# DDR.net
KiCad netlist of a schematic drawn in Altium Designer
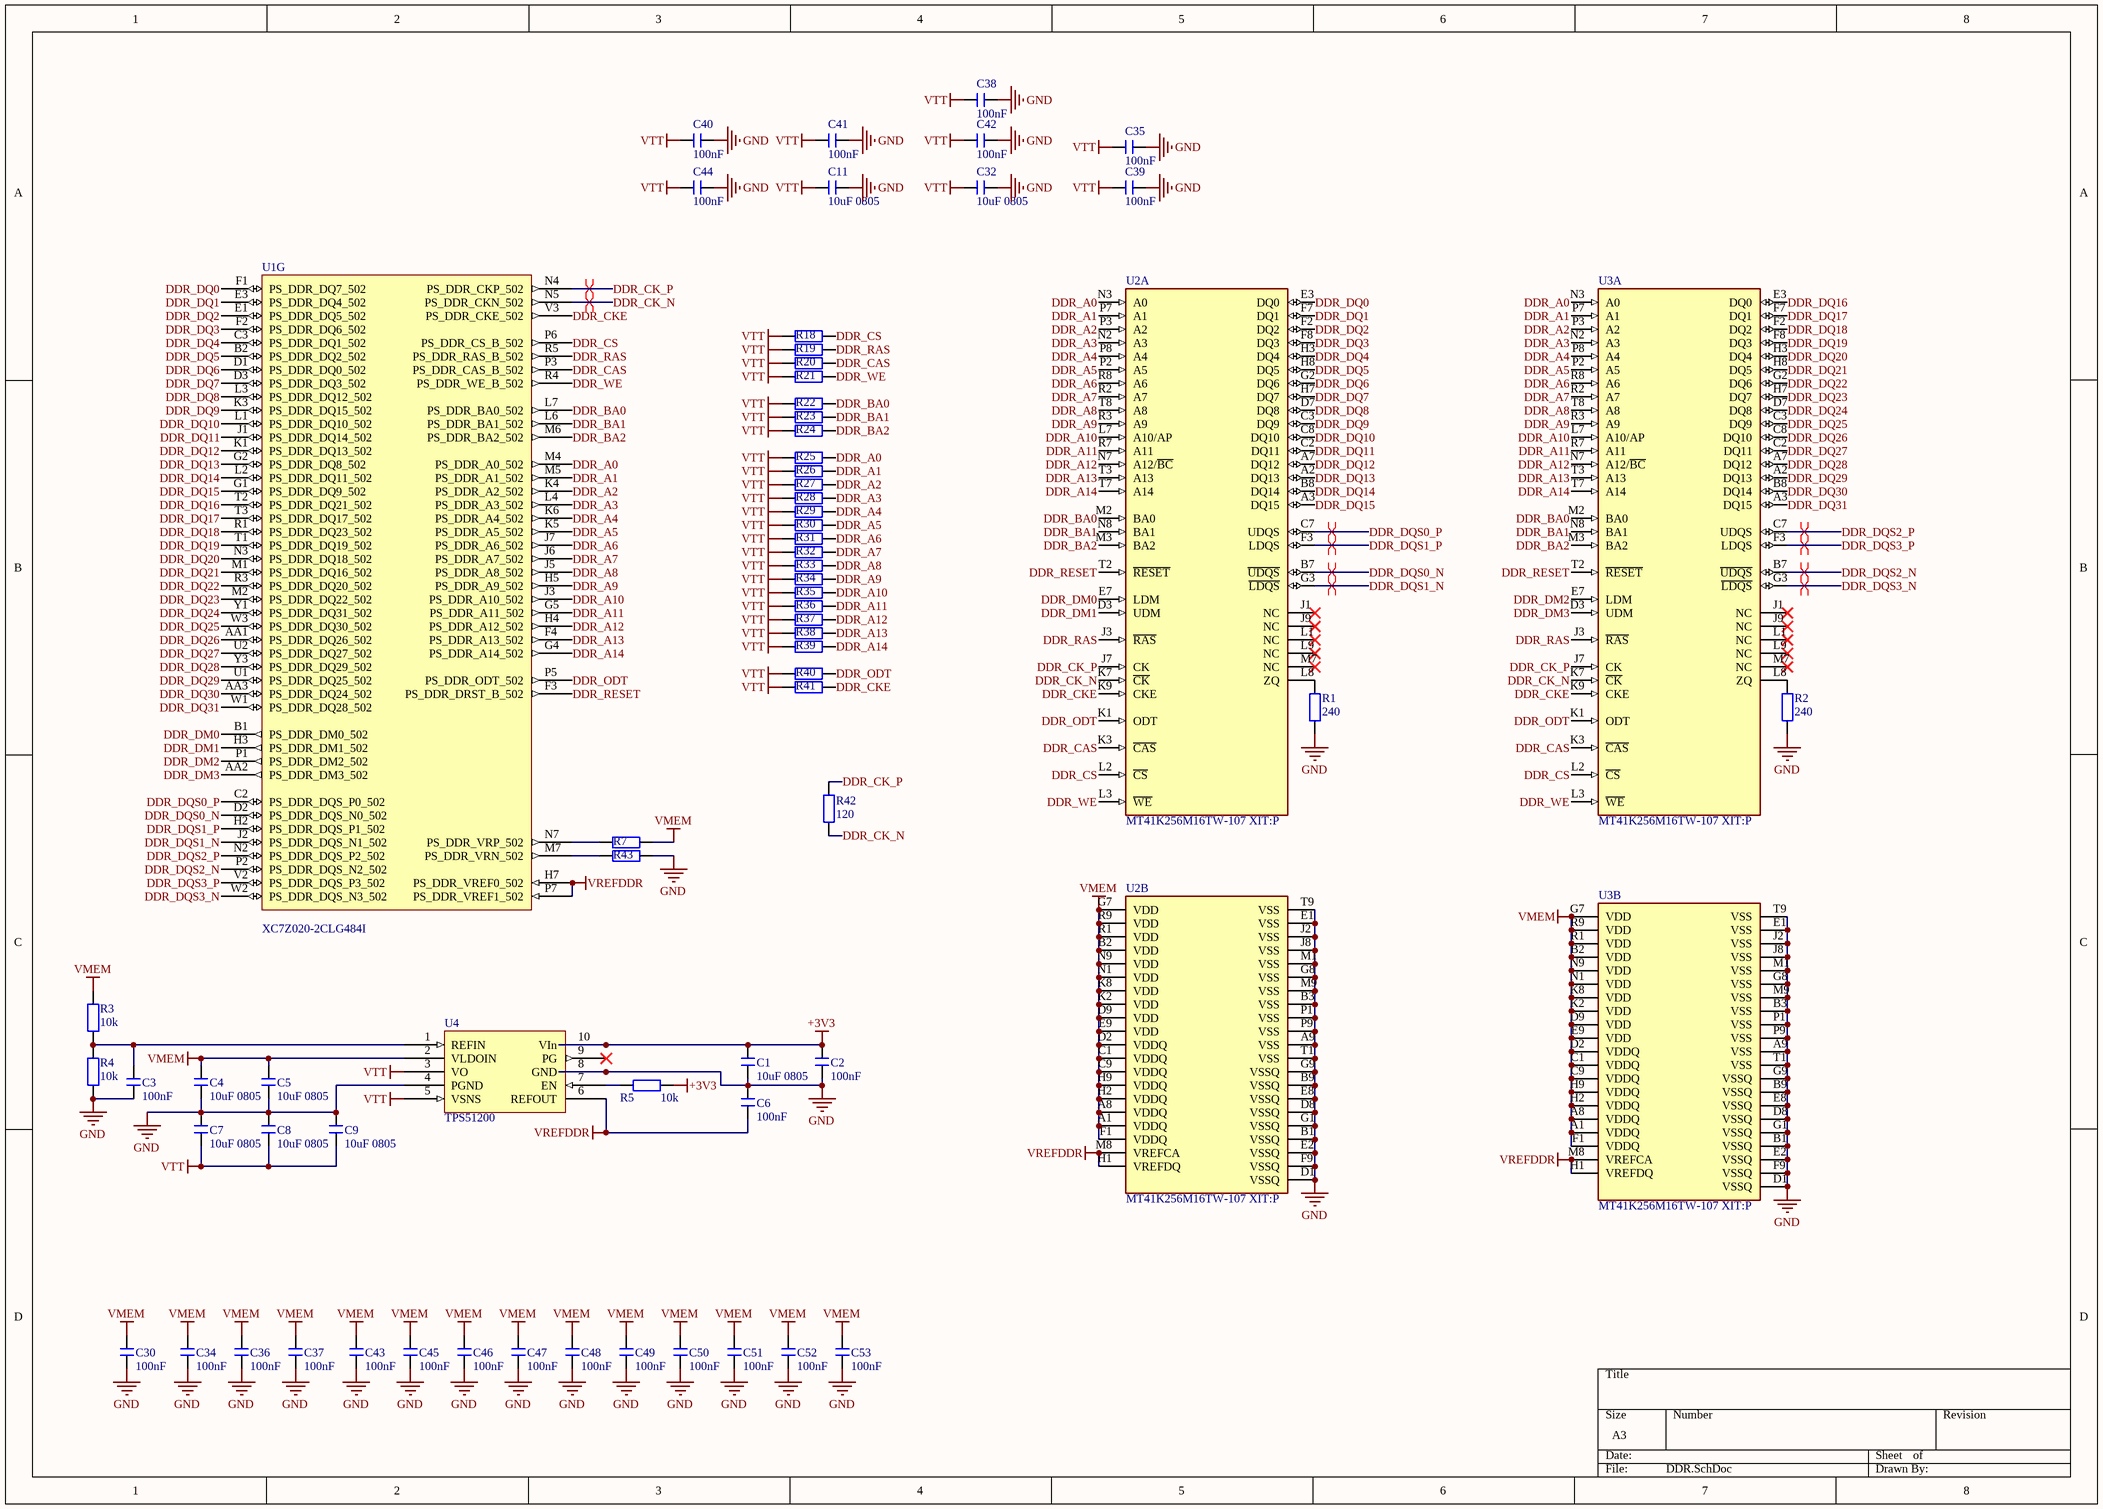
[diagram p0: DDR.SchDoc]

(export (version "E")
  (design (tool "Eeschema 10.0.6"))
  (components
    (comp (ref "C1") (value "10uF 0805") (footprint "C0603") (libsource (lib "Passive") (part "C")))
    (comp (ref "C2") (value "100nF") (footprint "C0402") (libsource (lib "Passive") (part "C")))
    (comp (ref "C3") (value "100nF") (footprint "C0402") (libsource (lib "Passive") (part "C")))
    (comp (ref "C4") (value "10uF 0805") (footprint "C0603") (libsource (lib "Passive") (part "C")))
    (comp (ref "C5") (value "10uF 0805") (footprint "C0603") (libsource (lib "Passive") (part "C")))
    (comp (ref "C6") (value "100nF") (footprint "C0402") (libsource (lib "Passive") (part "C")))
    (comp (ref "C7") (value "10uF 0805") (footprint "C0603") (libsource (lib "Passive") (part "C")))
    (comp (ref "C8") (value "10uF 0805") (footprint "C0603") (libsource (lib "Passive") (part "C")))
    (comp (ref "C9") (value "10uF 0805") (footprint "C0603") (libsource (lib "Passive") (part "C")))
    (comp (ref "C11") (value "10uF 0805") (footprint "C0603") (libsource (lib "Passive") (part "C")))
    (comp (ref "C30") (value "100nF") (footprint "C0402") (libsource (lib "Passive") (part "C")))
    (comp (ref "C32") (value "10uF 0805") (footprint "C0603") (libsource (lib "Passive") (part "C")))
    (comp (ref "C34") (value "100nF") (footprint "C0402") (libsource (lib "Passive") (part "C")))
    (comp (ref "C35") (value "100nF") (footprint "C0402") (libsource (lib "Passive") (part "C")))
    (comp (ref "C36") (value "100nF") (footprint "C0402") (libsource (lib "Passive") (part "C")))
    (comp (ref "C37") (value "100nF") (footprint "C0402") (libsource (lib "Passive") (part "C")))
    (comp (ref "C38") (value "100nF") (footprint "C0402") (libsource (lib "Passive") (part "C")))
    (comp (ref "C39") (value "100nF") (footprint "C0402") (libsource (lib "Passive") (part "C")))
    (comp (ref "C40") (value "100nF") (footprint "C0402") (libsource (lib "Passive") (part "C")))
    (comp (ref "C41") (value "100nF") (footprint "C0402") (libsource (lib "Passive") (part "C")))
    (comp (ref "C42") (value "100nF") (footprint "C0402") (libsource (lib "Passive") (part "C")))
    (comp (ref "C43") (value "100nF") (footprint "C0402") (libsource (lib "Passive") (part "C")))
    (comp (ref "C44") (value "100nF") (footprint "C0402") (libsource (lib "Passive") (part "C")))
    (comp (ref "C45") (value "100nF") (footprint "C0402") (libsource (lib "Passive") (part "C")))
    (comp (ref "C46") (value "100nF") (footprint "C0402") (libsource (lib "Passive") (part "C")))
    (comp (ref "C47") (value "100nF") (footprint "C0402") (libsource (lib "Passive") (part "C")))
    (comp (ref "C48") (value "100nF") (footprint "C0402") (libsource (lib "Passive") (part "C")))
    (comp (ref "C49") (value "100nF") (footprint "C0402") (libsource (lib "Passive") (part "C")))
    (comp (ref "C50") (value "100nF") (footprint "C0402") (libsource (lib "Passive") (part "C")))
    (comp (ref "C51") (value "100nF") (footprint "C0402") (libsource (lib "Passive") (part "C")))
    (comp (ref "C52") (value "100nF") (footprint "C0402") (libsource (lib "Passive") (part "C")))
    (comp (ref "C53") (value "100nF") (footprint "C0402") (libsource (lib "Passive") (part "C")))
    (comp (ref "R1") (value "240") (footprint "R0402") (libsource (lib "Passive") (part "R")))
    (comp (ref "R2") (value "240") (footprint "R0402") (libsource (lib "Passive") (part "R")))
    (comp (ref "R3") (value "10k") (footprint "R0402") (libsource (lib "Passive") (part "R")))
    (comp (ref "R4") (value "10k") (footprint "R0402") (libsource (lib "Passive") (part "R")))
    (comp (ref "R5") (value "10k") (footprint "R0402") (libsource (lib "Passive") (part "R")))
    (comp (ref "R7") (value "49.9") (footprint "R0402") (libsource (lib "Passive") (part "R")))
    (comp (ref "R18") (value "49.9") (footprint "R0402") (libsource (lib "Passive") (part "R")))
    (comp (ref "R19") (value "49.9") (footprint "R0402") (libsource (lib "Passive") (part "R")))
    (comp (ref "R20") (value "49.9") (footprint "R0402") (libsource (lib "Passive") (part "R")))
    (comp (ref "R21") (value "49.9") (footprint "R0402") (libsource (lib "Passive") (part "R")))
    (comp (ref "R22") (value "49.9") (footprint "R0402") (libsource (lib "Passive") (part "R")))
    (comp (ref "R23") (value "49.9") (footprint "R0402") (libsource (lib "Passive") (part "R")))
    (comp (ref "R24") (value "49.9") (footprint "R0402") (libsource (lib "Passive") (part "R")))
    (comp (ref "R25") (value "49.9") (footprint "R0402") (libsource (lib "Passive") (part "R")))
    (comp (ref "R26") (value "49.9") (footprint "R0402") (libsource (lib "Passive") (part "R")))
    (comp (ref "R27") (value "49.9") (footprint "R0402") (libsource (lib "Passive") (part "R")))
    (comp (ref "R28") (value "49.9") (footprint "R0402") (libsource (lib "Passive") (part "R")))
    (comp (ref "R29") (value "49.9") (footprint "R0402") (libsource (lib "Passive") (part "R")))
    (comp (ref "R30") (value "49.9") (footprint "R0402") (libsource (lib "Passive") (part "R")))
    (comp (ref "R31") (value "49.9") (footprint "R0402") (libsource (lib "Passive") (part "R")))
    (comp (ref "R32") (value "49.9") (footprint "R0402") (libsource (lib "Passive") (part "R")))
    (comp (ref "R33") (value "49.9") (footprint "R0402") (libsource (lib "Passive") (part "R")))
    (comp (ref "R34") (value "49.9") (footprint "R0402") (libsource (lib "Passive") (part "R")))
    (comp (ref "R35") (value "49.9") (footprint "R0402") (libsource (lib "Passive") (part "R")))
    (comp (ref "R36") (value "49.9") (footprint "R0402") (libsource (lib "Passive") (part "R")))
    (comp (ref "R37") (value "49.9") (footprint "R0402") (libsource (lib "Passive") (part "R")))
    (comp (ref "R38") (value "49.9") (footprint "R0402") (libsource (lib "Passive") (part "R")))
    (comp (ref "R39") (value "49.9") (footprint "R0402") (libsource (lib "Passive") (part "R")))
    (comp (ref "R40") (value "49.9") (footprint "R0402") (libsource (lib "Passive") (part "R")))
    (comp (ref "R41") (value "49.9") (footprint "R0402") (libsource (lib "Passive") (part "R")))
    (comp (ref "R42") (value "120") (footprint "R0402") (libsource (lib "Passive") (part "R")))
    (comp (ref "R43") (value "49.9") (footprint "R0402") (libsource (lib "Passive") (part "R")))
    (comp (ref "U1")
      (value "XC7Z020-2CLG484I")
      (footprint "CLG484")
      (fields (field (name "GENERIC PART NUMBER") "XC7Z020"))
      (libsource (lib "Altium Content Vault") (part "XNLX-XC7Z020-CLG484"))
    )
    (comp (ref "U2")
      (value "MT41K256M16TW-107 XIT:P")
      (footprint "FP-TW-MFG")
      (description "IC DRAM 4GBIT PARALLEL 96FBGA")
      (libsource (lib "Altium Content Vault") (part "c1579f81ec1b908b919197b6bca2eab"))
    )
    (comp (ref "U3")
      (value "MT41K256M16TW-107 XIT:P")
      (footprint "FP-TW-MFG")
      (description "IC DRAM 4GBIT PARALLEL 96FBGA")
      (libsource (lib "Altium Content Vault") (part "c1579f81ec1b908b919197b6bca2eab"))
    )
    (comp (ref "U4")
      (value "TPS51200")
      (footprint "SON50P300X100_HS-11N")
      (description "Sink and Source DDR Termination Regulator")
      (libsource (lib "TI") (part "TPS51200"))
    )
  )
  (nets
    (net (code "1") (name "+3V3") (class "Default")
      (node (ref "C1") (pin "2") (pinfunction "2_2") (pintype "passive"))
      (node (ref "C2") (pin "2") (pinfunction "2_2") (pintype "passive"))
      (node (ref "R5") (pin "2") (pinfunction "2_2") (pintype "passive"))
      (node (ref "U4") (pin "10") (pinfunction "VIn_10") (pintype "power_in"))
    )
    (net (code "2") (name "/DDR_A0") (class "Default")
      (node (ref "R25") (pin "2") (pinfunction "2_2") (pintype "passive"))
      (node (ref "U1") (pin "M4") (pinfunction "PS_DDR_A0_502_M4") (pintype "output"))
      (node (ref "U2") (pin "N3") (pinfunction "A0_N3") (pintype "input"))
      (node (ref "U3") (pin "N3") (pinfunction "A0_N3") (pintype "input"))
    )
    (net (code "3") (name "/DDR_A1") (class "Default")
      (node (ref "R26") (pin "2") (pinfunction "2_2") (pintype "passive"))
      (node (ref "U1") (pin "M5") (pinfunction "PS_DDR_A1_502_M5") (pintype "output"))
      (node (ref "U2") (pin "P7") (pinfunction "A1_P7") (pintype "input"))
      (node (ref "U3") (pin "P7") (pinfunction "A1_P7") (pintype "input"))
    )
    (net (code "4") (name "/DDR_A2") (class "Default")
      (node (ref "R27") (pin "2") (pinfunction "2_2") (pintype "passive"))
      (node (ref "U1") (pin "K4") (pinfunction "PS_DDR_A2_502_K4") (pintype "output"))
      (node (ref "U2") (pin "P3") (pinfunction "A2_P3") (pintype "input"))
      (node (ref "U3") (pin "P3") (pinfunction "A2_P3") (pintype "input"))
    )
    (net (code "5") (name "/DDR_A3") (class "Default")
      (node (ref "R28") (pin "2") (pinfunction "2_2") (pintype "passive"))
      (node (ref "U1") (pin "L4") (pinfunction "PS_DDR_A3_502_L4") (pintype "output"))
      (node (ref "U2") (pin "N2") (pinfunction "A3_N2") (pintype "input"))
      (node (ref "U3") (pin "N2") (pinfunction "A3_N2") (pintype "input"))
    )
    (net (code "6") (name "/DDR_A4") (class "Default")
      (node (ref "R29") (pin "2") (pinfunction "2_2") (pintype "passive"))
      (node (ref "U1") (pin "K6") (pinfunction "PS_DDR_A4_502_K6") (pintype "output"))
      (node (ref "U2") (pin "P8") (pinfunction "A4_P8") (pintype "input"))
      (node (ref "U3") (pin "P8") (pinfunction "A4_P8") (pintype "input"))
    )
    (net (code "7") (name "/DDR_A5") (class "Default")
      (node (ref "R30") (pin "2") (pinfunction "2_2") (pintype "passive"))
      (node (ref "U1") (pin "K5") (pinfunction "PS_DDR_A5_502_K5") (pintype "output"))
      (node (ref "U2") (pin "P2") (pinfunction "A5_P2") (pintype "input"))
      (node (ref "U3") (pin "P2") (pinfunction "A5_P2") (pintype "input"))
    )
    (net (code "8") (name "/DDR_A6") (class "Default")
      (node (ref "R31") (pin "2") (pinfunction "2_2") (pintype "passive"))
      (node (ref "U1") (pin "J7") (pinfunction "PS_DDR_A6_502_J7") (pintype "output"))
      (node (ref "U2") (pin "R8") (pinfunction "A6_R8") (pintype "input"))
      (node (ref "U3") (pin "R8") (pinfunction "A6_R8") (pintype "input"))
    )
    (net (code "9") (name "/DDR_A7") (class "Default")
      (node (ref "R32") (pin "2") (pinfunction "2_2") (pintype "passive"))
      (node (ref "U1") (pin "J6") (pinfunction "PS_DDR_A7_502_J6") (pintype "output"))
      (node (ref "U2") (pin "R2") (pinfunction "A7_R2") (pintype "input"))
      (node (ref "U3") (pin "R2") (pinfunction "A7_R2") (pintype "input"))
    )
    (net (code "10") (name "/DDR_A8") (class "Default")
      (node (ref "R33") (pin "2") (pinfunction "2_2") (pintype "passive"))
      (node (ref "U1") (pin "J5") (pinfunction "PS_DDR_A8_502_J5") (pintype "output"))
      (node (ref "U2") (pin "T8") (pinfunction "A8_T8") (pintype "input"))
      (node (ref "U3") (pin "T8") (pinfunction "A8_T8") (pintype "input"))
    )
    (net (code "11") (name "/DDR_A9") (class "Default")
      (node (ref "R34") (pin "2") (pinfunction "2_2") (pintype "passive"))
      (node (ref "U1") (pin "H5") (pinfunction "PS_DDR_A9_502_H5") (pintype "output"))
      (node (ref "U2") (pin "R3") (pinfunction "A9_R3") (pintype "input"))
      (node (ref "U3") (pin "R3") (pinfunction "A9_R3") (pintype "input"))
    )
    (net (code "12") (name "/DDR_A10") (class "Default")
      (node (ref "R35") (pin "2") (pinfunction "2_2") (pintype "passive"))
      (node (ref "U1") (pin "J3") (pinfunction "PS_DDR_A10_502_J3") (pintype "output"))
      (node (ref "U2") (pin "L7") (pinfunction "A10/AP_L7") (pintype "input"))
      (node (ref "U3") (pin "L7") (pinfunction "A10/AP_L7") (pintype "input"))
    )
    (net (code "13") (name "/DDR_A11") (class "Default")
      (node (ref "R36") (pin "2") (pinfunction "2_2") (pintype "passive"))
      (node (ref "U1") (pin "G5") (pinfunction "PS_DDR_A11_502_G5") (pintype "output"))
      (node (ref "U2") (pin "R7") (pinfunction "A11_R7") (pintype "input"))
      (node (ref "U3") (pin "R7") (pinfunction "A11_R7") (pintype "input"))
    )
    (net (code "14") (name "/DDR_A12") (class "Default")
      (node (ref "R37") (pin "2") (pinfunction "2_2") (pintype "passive"))
      (node (ref "U1") (pin "H4") (pinfunction "PS_DDR_A12_502_H4") (pintype "output"))
      (node (ref "U2") (pin "N7") (pinfunction "A12/~{BC}_N7") (pintype "input"))
      (node (ref "U3") (pin "N7") (pinfunction "A12/~{BC}_N7") (pintype "input"))
    )
    (net (code "15") (name "/DDR_A13") (class "Default")
      (node (ref "R38") (pin "2") (pinfunction "2_2") (pintype "passive"))
      (node (ref "U1") (pin "F4") (pinfunction "PS_DDR_A13_502_F4") (pintype "output"))
      (node (ref "U2") (pin "T3") (pinfunction "A13_T3") (pintype "input"))
      (node (ref "U3") (pin "T3") (pinfunction "A13_T3") (pintype "input"))
    )
    (net (code "16") (name "/DDR_A14") (class "Default")
      (node (ref "R39") (pin "2") (pinfunction "2_2") (pintype "passive"))
      (node (ref "U1") (pin "G4") (pinfunction "PS_DDR_A14_502_G4") (pintype "output"))
      (node (ref "U2") (pin "T7") (pinfunction "A14_T7") (pintype "input"))
      (node (ref "U3") (pin "T7") (pinfunction "A14_T7") (pintype "input"))
    )
    (net (code "17") (name "/DDR_BA0") (class "Default")
      (node (ref "R22") (pin "2") (pinfunction "2_2") (pintype "passive"))
      (node (ref "U1") (pin "L7") (pinfunction "PS_DDR_BA0_502_L7") (pintype "output"))
      (node (ref "U2") (pin "M2") (pinfunction "BA0_M2") (pintype "input"))
      (node (ref "U3") (pin "M2") (pinfunction "BA0_M2") (pintype "input"))
    )
    (net (code "18") (name "/DDR_BA1") (class "Default")
      (node (ref "R23") (pin "2") (pinfunction "2_2") (pintype "passive"))
      (node (ref "U1") (pin "L6") (pinfunction "PS_DDR_BA1_502_L6") (pintype "output"))
      (node (ref "U2") (pin "N8") (pinfunction "BA1_N8") (pintype "input"))
      (node (ref "U3") (pin "N8") (pinfunction "BA1_N8") (pintype "input"))
    )
    (net (code "19") (name "/DDR_BA2") (class "Default")
      (node (ref "R24") (pin "2") (pinfunction "2_2") (pintype "passive"))
      (node (ref "U1") (pin "M6") (pinfunction "PS_DDR_BA2_502_M6") (pintype "output"))
      (node (ref "U2") (pin "M3") (pinfunction "BA2_M3") (pintype "input"))
      (node (ref "U3") (pin "M3") (pinfunction "BA2_M3") (pintype "input"))
    )
    (net (code "20") (name "/DDR_CAS") (class "Default")
      (node (ref "R20") (pin "2") (pinfunction "2_2") (pintype "passive"))
      (node (ref "U1") (pin "P3") (pinfunction "PS_DDR_CAS_B_502_P3") (pintype "output"))
      (node (ref "U2") (pin "K3") (pinfunction "~{CAS}_K3") (pintype "input"))
      (node (ref "U3") (pin "K3") (pinfunction "~{CAS}_K3") (pintype "input"))
    )
    (net (code "21") (name "/DDR_CKE") (class "Default")
      (node (ref "R41") (pin "2") (pinfunction "2_2") (pintype "passive"))
      (node (ref "U1") (pin "V3") (pinfunction "PS_DDR_CKE_502_V3") (pintype "output"))
      (node (ref "U2") (pin "K9") (pinfunction "CKE_K9") (pintype "input"))
      (node (ref "U3") (pin "K9") (pinfunction "CKE_K9") (pintype "input"))
    )
    (net (code "22") (name "/DDR_CK_N") (class "Default")
      (node (ref "R42") (pin "1") (pinfunction "1_1") (pintype "passive"))
      (node (ref "U1") (pin "N5") (pinfunction "PS_DDR_CKN_502_N5") (pintype "output"))
      (node (ref "U2") (pin "K7") (pinfunction "~{CK}_K7") (pintype "input"))
      (node (ref "U3") (pin "K7") (pinfunction "~{CK}_K7") (pintype "input"))
    )
    (net (code "23") (name "/DDR_CK_P") (class "Default")
      (node (ref "R42") (pin "2") (pinfunction "2_2") (pintype "passive"))
      (node (ref "U1") (pin "N4") (pinfunction "PS_DDR_CKP_502_N4") (pintype "output"))
      (node (ref "U2") (pin "J7") (pinfunction "CK_J7") (pintype "input"))
      (node (ref "U3") (pin "J7") (pinfunction "CK_J7") (pintype "input"))
    )
    (net (code "24") (name "/DDR_CS") (class "Default")
      (node (ref "R18") (pin "2") (pinfunction "2_2") (pintype "passive"))
      (node (ref "U1") (pin "P6") (pinfunction "PS_DDR_CS_B_502_P6") (pintype "output"))
      (node (ref "U2") (pin "L2") (pinfunction "~{CS}_L2") (pintype "input"))
      (node (ref "U3") (pin "L2") (pinfunction "~{CS}_L2") (pintype "input"))
    )
    (net (code "25") (name "/DDR_DM0") (class "Default")
      (node (ref "U1") (pin "B1") (pinfunction "PS_DDR_DM0_502_B1") (pintype "output"))
      (node (ref "U2") (pin "E7") (pinfunction "LDM_E7") (pintype "input"))
    )
    (net (code "26") (name "/DDR_DM1") (class "Default")
      (node (ref "U1") (pin "H3") (pinfunction "PS_DDR_DM1_502_H3") (pintype "output"))
      (node (ref "U2") (pin "D3") (pinfunction "UDM_D3") (pintype "input"))
    )
    (net (code "27") (name "/DDR_DM2") (class "Default")
      (node (ref "U1") (pin "P1") (pinfunction "PS_DDR_DM2_502_P1") (pintype "output"))
      (node (ref "U3") (pin "E7") (pinfunction "LDM_E7") (pintype "input"))
    )
    (net (code "28") (name "/DDR_DM3") (class "Default")
      (node (ref "U1") (pin "AA2") (pinfunction "PS_DDR_DM3_502_AA2") (pintype "output"))
      (node (ref "U3") (pin "D3") (pinfunction "UDM_D3") (pintype "input"))
    )
    (net (code "29") (name "/DDR_DQ0") (class "Default")
      (node (ref "U1") (pin "F1") (pinfunction "PS_DDR_DQ7_502_F1") (pintype "bidirectional"))
      (node (ref "U2") (pin "E3") (pinfunction "DQ0_E3") (pintype "bidirectional"))
    )
    (net (code "30") (name "/DDR_DQ1") (class "Default")
      (node (ref "U1") (pin "E3") (pinfunction "PS_DDR_DQ4_502_E3") (pintype "bidirectional"))
      (node (ref "U2") (pin "F7") (pinfunction "DQ1_F7") (pintype "bidirectional"))
    )
    (net (code "31") (name "/DDR_DQ2") (class "Default")
      (node (ref "U1") (pin "E1") (pinfunction "PS_DDR_DQ5_502_E1") (pintype "bidirectional"))
      (node (ref "U2") (pin "F2") (pinfunction "DQ2_F2") (pintype "bidirectional"))
    )
    (net (code "32") (name "/DDR_DQ3") (class "Default")
      (node (ref "U1") (pin "F2") (pinfunction "PS_DDR_DQ6_502_F2") (pintype "bidirectional"))
      (node (ref "U2") (pin "F8") (pinfunction "DQ3_F8") (pintype "bidirectional"))
    )
    (net (code "33") (name "/DDR_DQ4") (class "Default")
      (node (ref "U1") (pin "C3") (pinfunction "PS_DDR_DQ1_502_C3") (pintype "bidirectional"))
      (node (ref "U2") (pin "H3") (pinfunction "DQ4_H3") (pintype "bidirectional"))
    )
    (net (code "34") (name "/DDR_DQ5") (class "Default")
      (node (ref "U1") (pin "B2") (pinfunction "PS_DDR_DQ2_502_B2") (pintype "bidirectional"))
      (node (ref "U2") (pin "H8") (pinfunction "DQ5_H8") (pintype "bidirectional"))
    )
    (net (code "35") (name "/DDR_DQ6") (class "Default")
      (node (ref "U1") (pin "D1") (pinfunction "PS_DDR_DQ0_502_D1") (pintype "bidirectional"))
      (node (ref "U2") (pin "G2") (pinfunction "DQ6_G2") (pintype "bidirectional"))
    )
    (net (code "36") (name "/DDR_DQ7") (class "Default")
      (node (ref "U1") (pin "D3") (pinfunction "PS_DDR_DQ3_502_D3") (pintype "bidirectional"))
      (node (ref "U2") (pin "H7") (pinfunction "DQ7_H7") (pintype "bidirectional"))
    )
    (net (code "37") (name "/DDR_DQ8") (class "Default")
      (node (ref "U1") (pin "L3") (pinfunction "PS_DDR_DQ12_502_L3") (pintype "bidirectional"))
      (node (ref "U2") (pin "D7") (pinfunction "DQ8_D7") (pintype "bidirectional"))
    )
    (net (code "38") (name "/DDR_DQ9") (class "Default")
      (node (ref "U1") (pin "K3") (pinfunction "PS_DDR_DQ15_502_K3") (pintype "bidirectional"))
      (node (ref "U2") (pin "C3") (pinfunction "DQ9_C3") (pintype "bidirectional"))
    )
    (net (code "39") (name "/DDR_DQ10") (class "Default")
      (node (ref "U1") (pin "L1") (pinfunction "PS_DDR_DQ10_502_L1") (pintype "bidirectional"))
      (node (ref "U2") (pin "C8") (pinfunction "DQ10_C8") (pintype "bidirectional"))
    )
    (net (code "40") (name "/DDR_DQ11") (class "Default")
      (node (ref "U1") (pin "J1") (pinfunction "PS_DDR_DQ14_502_J1") (pintype "bidirectional"))
      (node (ref "U2") (pin "C2") (pinfunction "DQ11_C2") (pintype "bidirectional"))
    )
    (net (code "41") (name "/DDR_DQ12") (class "Default")
      (node (ref "U1") (pin "K1") (pinfunction "PS_DDR_DQ13_502_K1") (pintype "bidirectional"))
      (node (ref "U2") (pin "A7") (pinfunction "DQ12_A7") (pintype "bidirectional"))
    )
    (net (code "42") (name "/DDR_DQ13") (class "Default")
      (node (ref "U1") (pin "G2") (pinfunction "PS_DDR_DQ8_502_G2") (pintype "bidirectional"))
      (node (ref "U2") (pin "A2") (pinfunction "DQ13_A2") (pintype "bidirectional"))
    )
    (net (code "43") (name "/DDR_DQ14") (class "Default")
      (node (ref "U1") (pin "L2") (pinfunction "PS_DDR_DQ11_502_L2") (pintype "bidirectional"))
      (node (ref "U2") (pin "B8") (pinfunction "DQ14_B8") (pintype "bidirectional"))
    )
    (net (code "44") (name "/DDR_DQ15") (class "Default")
      (node (ref "U1") (pin "G1") (pinfunction "PS_DDR_DQ9_502_G1") (pintype "bidirectional"))
      (node (ref "U2") (pin "A3") (pinfunction "DQ15_A3") (pintype "bidirectional"))
    )
    (net (code "45") (name "/DDR_DQ16") (class "Default")
      (node (ref "U1") (pin "T2") (pinfunction "PS_DDR_DQ21_502_T2") (pintype "bidirectional"))
      (node (ref "U3") (pin "E3") (pinfunction "DQ0_E3") (pintype "bidirectional"))
    )
    (net (code "46") (name "/DDR_DQ17") (class "Default")
      (node (ref "U1") (pin "T3") (pinfunction "PS_DDR_DQ17_502_T3") (pintype "bidirectional"))
      (node (ref "U3") (pin "F7") (pinfunction "DQ1_F7") (pintype "bidirectional"))
    )
    (net (code "47") (name "/DDR_DQ18") (class "Default")
      (node (ref "U1") (pin "R1") (pinfunction "PS_DDR_DQ23_502_R1") (pintype "bidirectional"))
      (node (ref "U3") (pin "F2") (pinfunction "DQ2_F2") (pintype "bidirectional"))
    )
    (net (code "48") (name "/DDR_DQ19") (class "Default")
      (node (ref "U1") (pin "T1") (pinfunction "PS_DDR_DQ19_502_T1") (pintype "bidirectional"))
      (node (ref "U3") (pin "F8") (pinfunction "DQ3_F8") (pintype "bidirectional"))
    )
    (net (code "49") (name "/DDR_DQ20") (class "Default")
      (node (ref "U1") (pin "N3") (pinfunction "PS_DDR_DQ18_502_N3") (pintype "bidirectional"))
      (node (ref "U3") (pin "H3") (pinfunction "DQ4_H3") (pintype "bidirectional"))
    )
    (net (code "50") (name "/DDR_DQ21") (class "Default")
      (node (ref "U1") (pin "M1") (pinfunction "PS_DDR_DQ16_502_M1") (pintype "bidirectional"))
      (node (ref "U3") (pin "H8") (pinfunction "DQ5_H8") (pintype "bidirectional"))
    )
    (net (code "51") (name "/DDR_DQ22") (class "Default")
      (node (ref "U1") (pin "R3") (pinfunction "PS_DDR_DQ20_502_R3") (pintype "bidirectional"))
      (node (ref "U3") (pin "G2") (pinfunction "DQ6_G2") (pintype "bidirectional"))
    )
    (net (code "52") (name "/DDR_DQ23") (class "Default")
      (node (ref "U1") (pin "M2") (pinfunction "PS_DDR_DQ22_502_M2") (pintype "bidirectional"))
      (node (ref "U3") (pin "H7") (pinfunction "DQ7_H7") (pintype "bidirectional"))
    )
    (net (code "53") (name "/DDR_DQ24") (class "Default")
      (node (ref "U1") (pin "Y1") (pinfunction "PS_DDR_DQ31_502_Y1") (pintype "bidirectional"))
      (node (ref "U3") (pin "D7") (pinfunction "DQ8_D7") (pintype "bidirectional"))
    )
    (net (code "54") (name "/DDR_DQ25") (class "Default")
      (node (ref "U1") (pin "W3") (pinfunction "PS_DDR_DQ30_502_W3") (pintype "bidirectional"))
      (node (ref "U3") (pin "C3") (pinfunction "DQ9_C3") (pintype "bidirectional"))
    )
    (net (code "55") (name "/DDR_DQ26") (class "Default")
      (node (ref "U1") (pin "AA1") (pinfunction "PS_DDR_DQ26_502_AA1") (pintype "bidirectional"))
      (node (ref "U3") (pin "C8") (pinfunction "DQ10_C8") (pintype "bidirectional"))
    )
    (net (code "56") (name "/DDR_DQ27") (class "Default")
      (node (ref "U1") (pin "U2") (pinfunction "PS_DDR_DQ27_502_U2") (pintype "bidirectional"))
      (node (ref "U3") (pin "C2") (pinfunction "DQ11_C2") (pintype "bidirectional"))
    )
    (net (code "57") (name "/DDR_DQ28") (class "Default")
      (node (ref "U1") (pin "Y3") (pinfunction "PS_DDR_DQ29_502_Y3") (pintype "bidirectional"))
      (node (ref "U3") (pin "A7") (pinfunction "DQ12_A7") (pintype "bidirectional"))
    )
    (net (code "58") (name "/DDR_DQ29") (class "Default")
      (node (ref "U1") (pin "U1") (pinfunction "PS_DDR_DQ25_502_U1") (pintype "bidirectional"))
      (node (ref "U3") (pin "A2") (pinfunction "DQ13_A2") (pintype "bidirectional"))
    )
    (net (code "59") (name "/DDR_DQ30") (class "Default")
      (node (ref "U1") (pin "AA3") (pinfunction "PS_DDR_DQ24_502_AA3") (pintype "bidirectional"))
      (node (ref "U3") (pin "B8") (pinfunction "DQ14_B8") (pintype "bidirectional"))
    )
    (net (code "60") (name "/DDR_DQ31") (class "Default")
      (node (ref "U1") (pin "W1") (pinfunction "PS_DDR_DQ28_502_W1") (pintype "bidirectional"))
      (node (ref "U3") (pin "A3") (pinfunction "DQ15_A3") (pintype "bidirectional"))
    )
    (net (code "61") (name "/DDR_DQS0_N") (class "Default")
      (node (ref "U1") (pin "D2") (pinfunction "PS_DDR_DQS_N0_502_D2") (pintype "bidirectional"))
      (node (ref "U2") (pin "B7") (pinfunction "~{UDQS}_B7") (pintype "bidirectional"))
    )
    (net (code "62") (name "/DDR_DQS0_P") (class "Default")
      (node (ref "U1") (pin "C2") (pinfunction "PS_DDR_DQS_P0_502_C2") (pintype "bidirectional"))
      (node (ref "U2") (pin "C7") (pinfunction "UDQS_C7") (pintype "bidirectional"))
    )
    (net (code "63") (name "/DDR_DQS1_N") (class "Default")
      (node (ref "U1") (pin "J2") (pinfunction "PS_DDR_DQS_N1_502_J2") (pintype "bidirectional"))
      (node (ref "U2") (pin "G3") (pinfunction "~{LDQS}_G3") (pintype "bidirectional"))
    )
    (net (code "64") (name "/DDR_DQS1_P") (class "Default")
      (node (ref "U1") (pin "H2") (pinfunction "PS_DDR_DQS_P1_502_H2") (pintype "bidirectional"))
      (node (ref "U2") (pin "F3") (pinfunction "LDQS_F3") (pintype "bidirectional"))
    )
    (net (code "65") (name "/DDR_DQS2_N") (class "Default")
      (node (ref "U1") (pin "P2") (pinfunction "PS_DDR_DQS_N2_502_P2") (pintype "bidirectional"))
      (node (ref "U3") (pin "B7") (pinfunction "~{UDQS}_B7") (pintype "bidirectional"))
    )
    (net (code "66") (name "/DDR_DQS2_P") (class "Default")
      (node (ref "U1") (pin "N2") (pinfunction "PS_DDR_DQS_P2_502_N2") (pintype "bidirectional"))
      (node (ref "U3") (pin "C7") (pinfunction "UDQS_C7") (pintype "bidirectional"))
    )
    (net (code "67") (name "/DDR_DQS3_N") (class "Default")
      (node (ref "U1") (pin "W2") (pinfunction "PS_DDR_DQS_N3_502_W2") (pintype "bidirectional"))
      (node (ref "U3") (pin "G3") (pinfunction "~{LDQS}_G3") (pintype "bidirectional"))
    )
    (net (code "68") (name "/DDR_DQS3_P") (class "Default")
      (node (ref "U1") (pin "V2") (pinfunction "PS_DDR_DQS_P3_502_V2") (pintype "bidirectional"))
      (node (ref "U3") (pin "F3") (pinfunction "LDQS_F3") (pintype "bidirectional"))
    )
    (net (code "69") (name "/DDR_ODT") (class "Default")
      (node (ref "R40") (pin "2") (pinfunction "2_2") (pintype "passive"))
      (node (ref "U1") (pin "P5") (pinfunction "PS_DDR_ODT_502_P5") (pintype "output"))
      (node (ref "U2") (pin "K1") (pinfunction "ODT_K1") (pintype "input"))
      (node (ref "U3") (pin "K1") (pinfunction "ODT_K1") (pintype "input"))
    )
    (net (code "70") (name "/DDR_RAS") (class "Default")
      (node (ref "R19") (pin "2") (pinfunction "2_2") (pintype "passive"))
      (node (ref "U1") (pin "R5") (pinfunction "PS_DDR_RAS_B_502_R5") (pintype "output"))
      (node (ref "U2") (pin "J3") (pinfunction "~{RAS}_J3") (pintype "input"))
      (node (ref "U3") (pin "J3") (pinfunction "~{RAS}_J3") (pintype "input"))
    )
    (net (code "71") (name "/DDR_RESET") (class "Default")
      (node (ref "U1") (pin "F3") (pinfunction "PS_DDR_DRST_B_502_F3") (pintype "output"))
      (node (ref "U2") (pin "T2") (pinfunction "~{RESET}_T2") (pintype "input"))
      (node (ref "U3") (pin "T2") (pinfunction "~{RESET}_T2") (pintype "input"))
    )
    (net (code "72") (name "/DDR_WE") (class "Default")
      (node (ref "R21") (pin "2") (pinfunction "2_2") (pintype "passive"))
      (node (ref "U1") (pin "R4") (pinfunction "PS_DDR_WE_B_502_R4") (pintype "output"))
      (node (ref "U2") (pin "L3") (pinfunction "~{WE}_L3") (pintype "input"))
      (node (ref "U3") (pin "L3") (pinfunction "~{WE}_L3") (pintype "input"))
    )
    (net (code "73") (name "GND") (class "Default")
      (node (ref "C1") (pin "1") (pinfunction "1_1") (pintype "passive"))
      (node (ref "C11") (pin "1") (pinfunction "1_1") (pintype "passive"))
      (node (ref "C2") (pin "1") (pinfunction "1_1") (pintype "passive"))
      (node (ref "C3") (pin "1") (pinfunction "1_1") (pintype "passive"))
      (node (ref "C30") (pin "1") (pinfunction "1_1") (pintype "passive"))
      (node (ref "C32") (pin "1") (pinfunction "1_1") (pintype "passive"))
      (node (ref "C34") (pin "1") (pinfunction "1_1") (pintype "passive"))
      (node (ref "C35") (pin "1") (pinfunction "1_1") (pintype "passive"))
      (node (ref "C36") (pin "1") (pinfunction "1_1") (pintype "passive"))
      (node (ref "C37") (pin "1") (pinfunction "1_1") (pintype "passive"))
      (node (ref "C38") (pin "1") (pinfunction "1_1") (pintype "passive"))
      (node (ref "C39") (pin "1") (pinfunction "1_1") (pintype "passive"))
      (node (ref "C4") (pin "1") (pinfunction "1_1") (pintype "passive"))
      (node (ref "C40") (pin "1") (pinfunction "1_1") (pintype "passive"))
      (node (ref "C41") (pin "1") (pinfunction "1_1") (pintype "passive"))
      (node (ref "C42") (pin "1") (pinfunction "1_1") (pintype "passive"))
      (node (ref "C43") (pin "1") (pinfunction "1_1") (pintype "passive"))
      (node (ref "C44") (pin "1") (pinfunction "1_1") (pintype "passive"))
      (node (ref "C45") (pin "1") (pinfunction "1_1") (pintype "passive"))
      (node (ref "C46") (pin "1") (pinfunction "1_1") (pintype "passive"))
      (node (ref "C47") (pin "1") (pinfunction "1_1") (pintype "passive"))
      (node (ref "C48") (pin "1") (pinfunction "1_1") (pintype "passive"))
      (node (ref "C49") (pin "1") (pinfunction "1_1") (pintype "passive"))
      (node (ref "C5") (pin "1") (pinfunction "1_1") (pintype "passive"))
      (node (ref "C50") (pin "1") (pinfunction "1_1") (pintype "passive"))
      (node (ref "C51") (pin "1") (pinfunction "1_1") (pintype "passive"))
      (node (ref "C52") (pin "1") (pinfunction "1_1") (pintype "passive"))
      (node (ref "C53") (pin "1") (pinfunction "1_1") (pintype "passive"))
      (node (ref "C6") (pin "2") (pinfunction "2_2") (pintype "passive"))
      (node (ref "C7") (pin "2") (pinfunction "2_2") (pintype "passive"))
      (node (ref "C8") (pin "2") (pinfunction "2_2") (pintype "passive"))
      (node (ref "C9") (pin "2") (pinfunction "2_2") (pintype "passive"))
      (node (ref "R1") (pin "2") (pinfunction "2_2") (pintype "passive"))
      (node (ref "R2") (pin "2") (pinfunction "2_2") (pintype "passive"))
      (node (ref "R4") (pin "2") (pinfunction "2_2") (pintype "passive"))
      (node (ref "R43") (pin "2") (pinfunction "2_2") (pintype "passive"))
      (node (ref "U2") (pin "A9") (pinfunction "VSS_A9") (pintype "power_in"))
      (node (ref "U2") (pin "B1") (pinfunction "VSSQ_B1") (pintype "power_in"))
      (node (ref "U2") (pin "B3") (pinfunction "VSS_B3") (pintype "power_in"))
      (node (ref "U2") (pin "B9") (pinfunction "VSSQ_B9") (pintype "power_in"))
      (node (ref "U2") (pin "D1") (pinfunction "VSSQ_D1") (pintype "power_in"))
      (node (ref "U2") (pin "D8") (pinfunction "VSSQ_D8") (pintype "power_in"))
      (node (ref "U2") (pin "E1") (pinfunction "VSS_E1") (pintype "power_in"))
      (node (ref "U2") (pin "E2") (pinfunction "VSSQ_E2") (pintype "power_in"))
      (node (ref "U2") (pin "E8") (pinfunction "VSSQ_E8") (pintype "power_in"))
      (node (ref "U2") (pin "F9") (pinfunction "VSSQ_F9") (pintype "power_in"))
      (node (ref "U2") (pin "G1") (pinfunction "VSSQ_G1") (pintype "power_in"))
      (node (ref "U2") (pin "G8") (pinfunction "VSS_G8") (pintype "power_in"))
      (node (ref "U2") (pin "G9") (pinfunction "VSSQ_G9") (pintype "power_in"))
      (node (ref "U2") (pin "J2") (pinfunction "VSS_J2") (pintype "power_in"))
      (node (ref "U2") (pin "J8") (pinfunction "VSS_J8") (pintype "power_in"))
      (node (ref "U2") (pin "M1") (pinfunction "VSS_M1") (pintype "power_in"))
      (node (ref "U2") (pin "M9") (pinfunction "VSS_M9") (pintype "power_in"))
      (node (ref "U2") (pin "P1") (pinfunction "VSS_P1") (pintype "power_in"))
      (node (ref "U2") (pin "P9") (pinfunction "VSS_P9") (pintype "power_in"))
      (node (ref "U2") (pin "T1") (pinfunction "VSS_T1") (pintype "power_in"))
      (node (ref "U2") (pin "T9") (pinfunction "VSS_T9") (pintype "power_in"))
      (node (ref "U3") (pin "A9") (pinfunction "VSS_A9") (pintype "power_in"))
      (node (ref "U3") (pin "B1") (pinfunction "VSSQ_B1") (pintype "power_in"))
      (node (ref "U3") (pin "B3") (pinfunction "VSS_B3") (pintype "power_in"))
      (node (ref "U3") (pin "B9") (pinfunction "VSSQ_B9") (pintype "power_in"))
      (node (ref "U3") (pin "D1") (pinfunction "VSSQ_D1") (pintype "power_in"))
      (node (ref "U3") (pin "D8") (pinfunction "VSSQ_D8") (pintype "power_in"))
      (node (ref "U3") (pin "E1") (pinfunction "VSS_E1") (pintype "power_in"))
      (node (ref "U3") (pin "E2") (pinfunction "VSSQ_E2") (pintype "power_in"))
      (node (ref "U3") (pin "E8") (pinfunction "VSSQ_E8") (pintype "power_in"))
      (node (ref "U3") (pin "F9") (pinfunction "VSSQ_F9") (pintype "power_in"))
      (node (ref "U3") (pin "G1") (pinfunction "VSSQ_G1") (pintype "power_in"))
      (node (ref "U3") (pin "G8") (pinfunction "VSS_G8") (pintype "power_in"))
      (node (ref "U3") (pin "G9") (pinfunction "VSSQ_G9") (pintype "power_in"))
      (node (ref "U3") (pin "J2") (pinfunction "VSS_J2") (pintype "power_in"))
      (node (ref "U3") (pin "J8") (pinfunction "VSS_J8") (pintype "power_in"))
      (node (ref "U3") (pin "M1") (pinfunction "VSS_M1") (pintype "power_in"))
      (node (ref "U3") (pin "M9") (pinfunction "VSS_M9") (pintype "power_in"))
      (node (ref "U3") (pin "P1") (pinfunction "VSS_P1") (pintype "power_in"))
      (node (ref "U3") (pin "P9") (pinfunction "VSS_P9") (pintype "power_in"))
      (node (ref "U3") (pin "T1") (pinfunction "VSS_T1") (pintype "power_in"))
      (node (ref "U3") (pin "T9") (pinfunction "VSS_T9") (pintype "power_in"))
      (node (ref "U4") (pin "4") (pinfunction "PGND_4") (pintype "power_in"))
      (node (ref "U4") (pin "8") (pinfunction "GND_8") (pintype "power_in"))
    )
    (net (code "74") (name "Net-(U1G-PS_DDR_VRN_502)") (class "Default")
      (node (ref "R43") (pin "1") (pinfunction "1_1") (pintype "passive"))
      (node (ref "U1") (pin "M7") (pinfunction "PS_DDR_VRN_502_M7") (pintype "output"))
    )
    (net (code "75") (name "Net-(U1G-PS_DDR_VRP_502)") (class "Default")
      (node (ref "R7") (pin "1") (pinfunction "1_1") (pintype "passive"))
      (node (ref "U1") (pin "N7") (pinfunction "PS_DDR_VRP_502_N7") (pintype "output"))
    )
    (net (code "76") (name "Net-(U2A-ZQ)") (class "Default")
      (node (ref "R1") (pin "1") (pinfunction "1_1") (pintype "passive"))
      (node (ref "U2") (pin "L8") (pinfunction "ZQ_L8") (pintype "passive"))
    )
    (net (code "77") (name "Net-(U3A-ZQ)") (class "Default")
      (node (ref "R2") (pin "1") (pinfunction "1_1") (pintype "passive"))
      (node (ref "U3") (pin "L8") (pinfunction "ZQ_L8") (pintype "passive"))
    )
    (net (code "78") (name "Net-(U4-EN)") (class "Default")
      (node (ref "R5") (pin "1") (pinfunction "1_1") (pintype "passive"))
      (node (ref "U4") (pin "7") (pinfunction "EN_7") (pintype "input"))
    )
    (net (code "79") (name "Net-(U4-REFIN)") (class "Default")
      (node (ref "C3") (pin "2") (pinfunction "2_2") (pintype "passive"))
      (node (ref "R3") (pin "2") (pinfunction "2_2") (pintype "passive"))
      (node (ref "R4") (pin "1") (pinfunction "1_1") (pintype "passive"))
      (node (ref "U4") (pin "1") (pinfunction "REFIN_1") (pintype "input"))
    )
    (net (code "80") (name "VMEM") (class "Default")
      (node (ref "C30") (pin "2") (pinfunction "2_2") (pintype "passive"))
      (node (ref "C34") (pin "2") (pinfunction "2_2") (pintype "passive"))
      (node (ref "C36") (pin "2") (pinfunction "2_2") (pintype "passive"))
      (node (ref "C37") (pin "2") (pinfunction "2_2") (pintype "passive"))
      (node (ref "C4") (pin "2") (pinfunction "2_2") (pintype "passive"))
      (node (ref "C43") (pin "2") (pinfunction "2_2") (pintype "passive"))
      (node (ref "C45") (pin "2") (pinfunction "2_2") (pintype "passive"))
      (node (ref "C46") (pin "2") (pinfunction "2_2") (pintype "passive"))
      (node (ref "C47") (pin "2") (pinfunction "2_2") (pintype "passive"))
      (node (ref "C48") (pin "2") (pinfunction "2_2") (pintype "passive"))
      (node (ref "C49") (pin "2") (pinfunction "2_2") (pintype "passive"))
      (node (ref "C5") (pin "2") (pinfunction "2_2") (pintype "passive"))
      (node (ref "C50") (pin "2") (pinfunction "2_2") (pintype "passive"))
      (node (ref "C51") (pin "2") (pinfunction "2_2") (pintype "passive"))
      (node (ref "C52") (pin "2") (pinfunction "2_2") (pintype "passive"))
      (node (ref "C53") (pin "2") (pinfunction "2_2") (pintype "passive"))
      (node (ref "R3") (pin "1") (pinfunction "1_1") (pintype "passive"))
      (node (ref "R7") (pin "2") (pinfunction "2_2") (pintype "passive"))
      (node (ref "U2") (pin "A1") (pinfunction "VDDQ_A1") (pintype "power_in"))
      (node (ref "U2") (pin "A8") (pinfunction "VDDQ_A8") (pintype "power_in"))
      (node (ref "U2") (pin "B2") (pinfunction "VDD_B2") (pintype "power_in"))
      (node (ref "U2") (pin "C1") (pinfunction "VDDQ_C1") (pintype "power_in"))
      (node (ref "U2") (pin "C9") (pinfunction "VDDQ_C9") (pintype "power_in"))
      (node (ref "U2") (pin "D2") (pinfunction "VDDQ_D2") (pintype "power_in"))
      (node (ref "U2") (pin "D9") (pinfunction "VDD_D9") (pintype "power_in"))
      (node (ref "U2") (pin "E9") (pinfunction "VDD_E9") (pintype "power_in"))
      (node (ref "U2") (pin "F1") (pinfunction "VDDQ_F1") (pintype "power_in"))
      (node (ref "U2") (pin "G7") (pinfunction "VDD_G7") (pintype "power_in"))
      (node (ref "U2") (pin "H2") (pinfunction "VDDQ_H2") (pintype "power_in"))
      (node (ref "U2") (pin "H9") (pinfunction "VDDQ_H9") (pintype "power_in"))
      (node (ref "U2") (pin "K2") (pinfunction "VDD_K2") (pintype "power_in"))
      (node (ref "U2") (pin "K8") (pinfunction "VDD_K8") (pintype "power_in"))
      (node (ref "U2") (pin "N1") (pinfunction "VDD_N1") (pintype "power_in"))
      (node (ref "U2") (pin "N9") (pinfunction "VDD_N9") (pintype "power_in"))
      (node (ref "U2") (pin "R1") (pinfunction "VDD_R1") (pintype "power_in"))
      (node (ref "U2") (pin "R9") (pinfunction "VDD_R9") (pintype "power_in"))
      (node (ref "U3") (pin "A1") (pinfunction "VDDQ_A1") (pintype "power_in"))
      (node (ref "U3") (pin "A8") (pinfunction "VDDQ_A8") (pintype "power_in"))
      (node (ref "U3") (pin "B2") (pinfunction "VDD_B2") (pintype "power_in"))
      (node (ref "U3") (pin "C1") (pinfunction "VDDQ_C1") (pintype "power_in"))
      (node (ref "U3") (pin "C9") (pinfunction "VDDQ_C9") (pintype "power_in"))
      (node (ref "U3") (pin "D2") (pinfunction "VDDQ_D2") (pintype "power_in"))
      (node (ref "U3") (pin "D9") (pinfunction "VDD_D9") (pintype "power_in"))
      (node (ref "U3") (pin "E9") (pinfunction "VDD_E9") (pintype "power_in"))
      (node (ref "U3") (pin "F1") (pinfunction "VDDQ_F1") (pintype "power_in"))
      (node (ref "U3") (pin "G7") (pinfunction "VDD_G7") (pintype "power_in"))
      (node (ref "U3") (pin "H2") (pinfunction "VDDQ_H2") (pintype "power_in"))
      (node (ref "U3") (pin "H9") (pinfunction "VDDQ_H9") (pintype "power_in"))
      (node (ref "U3") (pin "K2") (pinfunction "VDD_K2") (pintype "power_in"))
      (node (ref "U3") (pin "K8") (pinfunction "VDD_K8") (pintype "power_in"))
      (node (ref "U3") (pin "N1") (pinfunction "VDD_N1") (pintype "power_in"))
      (node (ref "U3") (pin "N9") (pinfunction "VDD_N9") (pintype "power_in"))
      (node (ref "U3") (pin "R1") (pinfunction "VDD_R1") (pintype "power_in"))
      (node (ref "U3") (pin "R9") (pinfunction "VDD_R9") (pintype "power_in"))
      (node (ref "U4") (pin "2") (pinfunction "VLDOIN_2") (pintype "power_in"))
    )
    (net (code "81") (name "VREFDDR") (class "Default")
      (node (ref "C6") (pin "1") (pinfunction "1_1") (pintype "passive"))
      (node (ref "U1") (pin "H7") (pinfunction "PS_DDR_VREF0_502_H7") (pintype "input"))
      (node (ref "U1") (pin "P7") (pinfunction "PS_DDR_VREF1_502_P7") (pintype "input"))
      (node (ref "U2") (pin "H1") (pinfunction "VREFDQ_H1") (pintype "power_in"))
      (node (ref "U2") (pin "M8") (pinfunction "VREFCA_M8") (pintype "power_in"))
      (node (ref "U3") (pin "H1") (pinfunction "VREFDQ_H1") (pintype "power_in"))
      (node (ref "U3") (pin "M8") (pinfunction "VREFCA_M8") (pintype "power_in"))
      (node (ref "U4") (pin "6") (pinfunction "REFOUT_6") (pintype "power_in"))
    )
    (net (code "82") (name "VTT") (class "Default")
      (node (ref "C11") (pin "2") (pinfunction "2_2") (pintype "passive"))
      (node (ref "C32") (pin "2") (pinfunction "2_2") (pintype "passive"))
      (node (ref "C35") (pin "2") (pinfunction "2_2") (pintype "passive"))
      (node (ref "C38") (pin "2") (pinfunction "2_2") (pintype "passive"))
      (node (ref "C39") (pin "2") (pinfunction "2_2") (pintype "passive"))
      (node (ref "C40") (pin "2") (pinfunction "2_2") (pintype "passive"))
      (node (ref "C41") (pin "2") (pinfunction "2_2") (pintype "passive"))
      (node (ref "C42") (pin "2") (pinfunction "2_2") (pintype "passive"))
      (node (ref "C44") (pin "2") (pinfunction "2_2") (pintype "passive"))
      (node (ref "C7") (pin "1") (pinfunction "1_1") (pintype "passive"))
      (node (ref "C8") (pin "1") (pinfunction "1_1") (pintype "passive"))
      (node (ref "C9") (pin "1") (pinfunction "1_1") (pintype "passive"))
      (node (ref "R18") (pin "1") (pinfunction "1_1") (pintype "passive"))
      (node (ref "R19") (pin "1") (pinfunction "1_1") (pintype "passive"))
      (node (ref "R20") (pin "1") (pinfunction "1_1") (pintype "passive"))
      (node (ref "R21") (pin "1") (pinfunction "1_1") (pintype "passive"))
      (node (ref "R22") (pin "1") (pinfunction "1_1") (pintype "passive"))
      (node (ref "R23") (pin "1") (pinfunction "1_1") (pintype "passive"))
      (node (ref "R24") (pin "1") (pinfunction "1_1") (pintype "passive"))
      (node (ref "R25") (pin "1") (pinfunction "1_1") (pintype "passive"))
      (node (ref "R26") (pin "1") (pinfunction "1_1") (pintype "passive"))
      (node (ref "R27") (pin "1") (pinfunction "1_1") (pintype "passive"))
      (node (ref "R28") (pin "1") (pinfunction "1_1") (pintype "passive"))
      (node (ref "R29") (pin "1") (pinfunction "1_1") (pintype "passive"))
      (node (ref "R30") (pin "1") (pinfunction "1_1") (pintype "passive"))
      (node (ref "R31") (pin "1") (pinfunction "1_1") (pintype "passive"))
      (node (ref "R32") (pin "1") (pinfunction "1_1") (pintype "passive"))
      (node (ref "R33") (pin "1") (pinfunction "1_1") (pintype "passive"))
      (node (ref "R34") (pin "1") (pinfunction "1_1") (pintype "passive"))
      (node (ref "R35") (pin "1") (pinfunction "1_1") (pintype "passive"))
      (node (ref "R36") (pin "1") (pinfunction "1_1") (pintype "passive"))
      (node (ref "R37") (pin "1") (pinfunction "1_1") (pintype "passive"))
      (node (ref "R38") (pin "1") (pinfunction "1_1") (pintype "passive"))
      (node (ref "R39") (pin "1") (pinfunction "1_1") (pintype "passive"))
      (node (ref "R40") (pin "1") (pinfunction "1_1") (pintype "passive"))
      (node (ref "R41") (pin "1") (pinfunction "1_1") (pintype "passive"))
      (node (ref "U4") (pin "3") (pinfunction "VO_3") (pintype "power_in"))
      (node (ref "U4") (pin "5") (pinfunction "VSNS_5") (pintype "input"))
    )
    (net (code "83") (name "unconnected-(U2A-NC-PadJ1)") (class "Default")
      (node (ref "U2") (pin "J1") (pinfunction "NC_J1") (pintype "passive+no_connect"))
    )
    (net (code "84") (name "unconnected-(U2A-NC-PadJ9)") (class "Default")
      (node (ref "U2") (pin "J9") (pinfunction "NC_J9") (pintype "passive+no_connect"))
    )
    (net (code "85") (name "unconnected-(U2A-NC-PadL1)") (class "Default")
      (node (ref "U2") (pin "L1") (pinfunction "NC_L1") (pintype "passive+no_connect"))
    )
    (net (code "86") (name "unconnected-(U2A-NC-PadL9)") (class "Default")
      (node (ref "U2") (pin "L9") (pinfunction "NC_L9") (pintype "passive+no_connect"))
    )
    (net (code "87") (name "unconnected-(U2A-NC-PadM7)") (class "Default")
      (node (ref "U2") (pin "M7") (pinfunction "NC_M7") (pintype "passive+no_connect"))
    )
    (net (code "88") (name "unconnected-(U3A-NC-PadJ1)") (class "Default")
      (node (ref "U3") (pin "J1") (pinfunction "NC_J1") (pintype "passive+no_connect"))
    )
    (net (code "89") (name "unconnected-(U3A-NC-PadJ9)") (class "Default")
      (node (ref "U3") (pin "J9") (pinfunction "NC_J9") (pintype "passive+no_connect"))
    )
    (net (code "90") (name "unconnected-(U3A-NC-PadL1)") (class "Default")
      (node (ref "U3") (pin "L1") (pinfunction "NC_L1") (pintype "passive+no_connect"))
    )
    (net (code "91") (name "unconnected-(U3A-NC-PadL9)") (class "Default")
      (node (ref "U3") (pin "L9") (pinfunction "NC_L9") (pintype "passive+no_connect"))
    )
    (net (code "92") (name "unconnected-(U3A-NC-PadM7)") (class "Default")
      (node (ref "U3") (pin "M7") (pinfunction "NC_M7") (pintype "passive+no_connect"))
    )
    (net (code "93") (name "unconnected-(U4-PG-Pad9)") (class "Default")
      (node (ref "U4") (pin "9") (pinfunction "PG_9") (pintype "output+no_connect"))
    )
  )
)
